# Led_hien_thi.net
KiCad netlist of a schematic drawn in Altium Designer
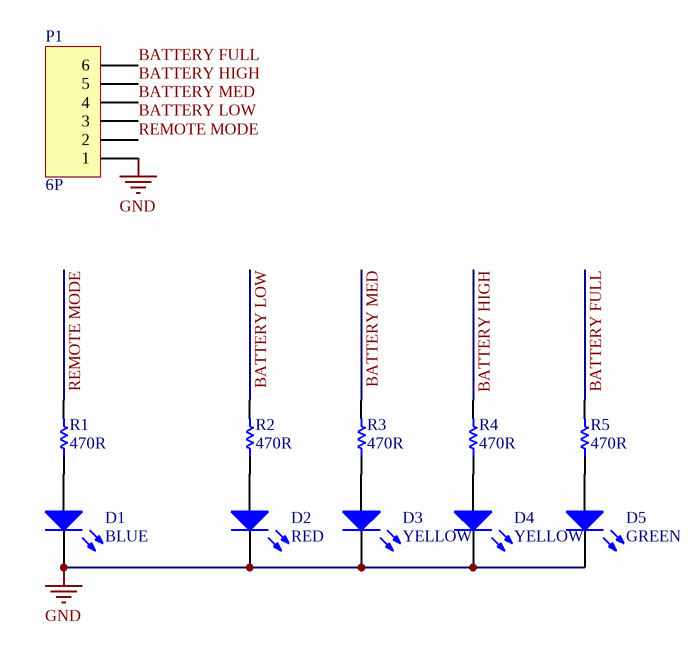
[diagram p0: Led hien thi.SchDoc]

(export (version "E")
  (design (tool "Eeschema 10.0.6"))
  (components
    (comp (ref "D1")
      (value "BLUE")
      (footprint "LED0805")
      (description "Typical INFRARED GaAs LED")
      (fields (field (name "Comment") "LED dán 0805BLUE") (field (name "PUBLISHER") "*"))
      (libsource (lib "DnsSchLib") (part "LED0"))
    )
    (comp (ref "D2")
      (value "RED")
      (footprint "LED0805")
      (description "Typical INFRARED GaAs LED")
      (fields (field (name "Comment") "LED dán 0805RED") (field (name "PUBLISHER") "*"))
      (libsource (lib "DnsSchLib") (part "LED0"))
    )
    (comp (ref "D3")
      (value "YELLOW")
      (footprint "LED0805")
      (description "Typical INFRARED GaAs LED")
      (fields (field (name "Comment") "LED dán 0805YELLOW") (field (name "PUBLISHER") "*"))
      (libsource (lib "DnsSchLib") (part "LED0"))
    )
    (comp (ref "D4")
      (value "YELLOW")
      (footprint "LED0805")
      (description "Typical INFRARED GaAs LED")
      (fields (field (name "Comment") "LED dán 0805YELLOW") (field (name "PUBLISHER") "*"))
      (libsource (lib "DnsSchLib") (part "LED0"))
    )
    (comp (ref "D5")
      (value "GREEN")
      (footprint "LED0805")
      (description "Typical INFRARED GaAs LED")
      (fields (field (name "Comment") "LED dán 0805GREEN") (field (name "PUBLISHER") "*"))
      (libsource (lib "DnsSchLib") (part "LED0"))
    )
    (comp (ref "P1")
      (value "6P")
      (footprint "HDR1X6H")
      (description "Header, 6-Pin, Right Angle")
      (fields
        (field (name "Comment") "Jump đực chân thẳng, 2.54mm 6P")
        (field (name "PUBLISHER") "Altium Limited")
      )
      (libsource (lib "Miscellaneous Connectors") (part "Header 6H"))
    )
    (comp (ref "R1")
      (value "470R")
      (footprint "0805DD")
      (description "Semiconductor Resistor")
      (fields (field (name "Comment") "Điện trở dán 0805470R") (field (name "PUBLISHER") "*"))
      (libsource (lib "DnsSchLib") (part "Res Semi"))
    )
    (comp (ref "R2")
      (value "470R")
      (footprint "0805DD")
      (description "Semiconductor Resistor")
      (fields (field (name "Comment") "Điện trở dán 0805470R") (field (name "PUBLISHER") "*"))
      (libsource (lib "DnsSchLib") (part "Res Semi"))
    )
    (comp (ref "R3")
      (value "470R")
      (footprint "0805DD")
      (description "Semiconductor Resistor")
      (fields (field (name "Comment") "Điện trở dán 0805470R") (field (name "PUBLISHER") "*"))
      (libsource (lib "DnsSchLib") (part "Res Semi"))
    )
    (comp (ref "R4")
      (value "470R")
      (footprint "0805DD")
      (description "Semiconductor Resistor")
      (fields (field (name "Comment") "Điện trở dán 0805470R") (field (name "PUBLISHER") "*"))
      (libsource (lib "DnsSchLib") (part "Res Semi"))
    )
    (comp (ref "R5")
      (value "470R")
      (footprint "0805DD")
      (description "Semiconductor Resistor")
      (fields (field (name "Comment") "Điện trở dán 0805470R") (field (name "PUBLISHER") "*"))
      (libsource (lib "DnsSchLib") (part "Res Semi"))
    )
  )
  (nets
    (net (code "1") (name "/BATTERY FULL") (class "Default")
      (node (ref "P1") (pin "6") (pinfunction "6_6") (pintype "passive"))
      (node (ref "R5") (pin "2") (pinfunction "2_2") (pintype "passive"))
    )
    (net (code "2") (name "/BATTERY HIGH") (class "Default")
      (node (ref "P1") (pin "5") (pinfunction "5_5") (pintype "passive"))
      (node (ref "R4") (pin "2") (pinfunction "2_2") (pintype "passive"))
    )
    (net (code "3") (name "/BATTERY LOW") (class "Default")
      (node (ref "P1") (pin "3") (pinfunction "3_3") (pintype "passive"))
      (node (ref "R2") (pin "2") (pinfunction "2_2") (pintype "passive"))
    )
    (net (code "4") (name "/BATTERY MED") (class "Default")
      (node (ref "P1") (pin "4") (pinfunction "4_4") (pintype "passive"))
      (node (ref "R3") (pin "2") (pinfunction "2_2") (pintype "passive"))
    )
    (net (code "5") (name "/REMOTE MODE") (class "Default")
      (node (ref "P1") (pin "2") (pinfunction "2_2") (pintype "passive"))
      (node (ref "R1") (pin "2") (pinfunction "2_2") (pintype "passive"))
    )
    (net (code "6") (name "GND") (class "Default")
      (node (ref "D1") (pin "2") (pinfunction "K_2") (pintype "passive"))
      (node (ref "D2") (pin "2") (pinfunction "K_2") (pintype "passive"))
      (node (ref "D3") (pin "2") (pinfunction "K_2") (pintype "passive"))
      (node (ref "D4") (pin "2") (pinfunction "K_2") (pintype "passive"))
      (node (ref "D5") (pin "2") (pinfunction "K_2") (pintype "passive"))
      (node (ref "P1") (pin "1") (pinfunction "1_1") (pintype "passive"))
    )
    (net (code "7") (name "Net-(D1-A)") (class "Default")
      (node (ref "D1") (pin "1") (pinfunction "A_1") (pintype "passive"))
      (node (ref "R1") (pin "1") (pinfunction "1_1") (pintype "passive"))
    )
    (net (code "8") (name "Net-(D2-A)") (class "Default")
      (node (ref "D2") (pin "1") (pinfunction "A_1") (pintype "passive"))
      (node (ref "R2") (pin "1") (pinfunction "1_1") (pintype "passive"))
    )
    (net (code "9") (name "Net-(D3-A)") (class "Default")
      (node (ref "D3") (pin "1") (pinfunction "A_1") (pintype "passive"))
      (node (ref "R3") (pin "1") (pinfunction "1_1") (pintype "passive"))
    )
    (net (code "10") (name "Net-(D4-A)") (class "Default")
      (node (ref "D4") (pin "1") (pinfunction "A_1") (pintype "passive"))
      (node (ref "R4") (pin "1") (pinfunction "1_1") (pintype "passive"))
    )
    (net (code "11") (name "Net-(D5-A)") (class "Default")
      (node (ref "D5") (pin "1") (pinfunction "A_1") (pintype "passive"))
      (node (ref "R5") (pin "1") (pinfunction "1_1") (pintype "passive"))
    )
  )
)
